# Ardy-Pro-Outlin-ev_3.net
KiCad netlist of a schematic drawn in EAGLE
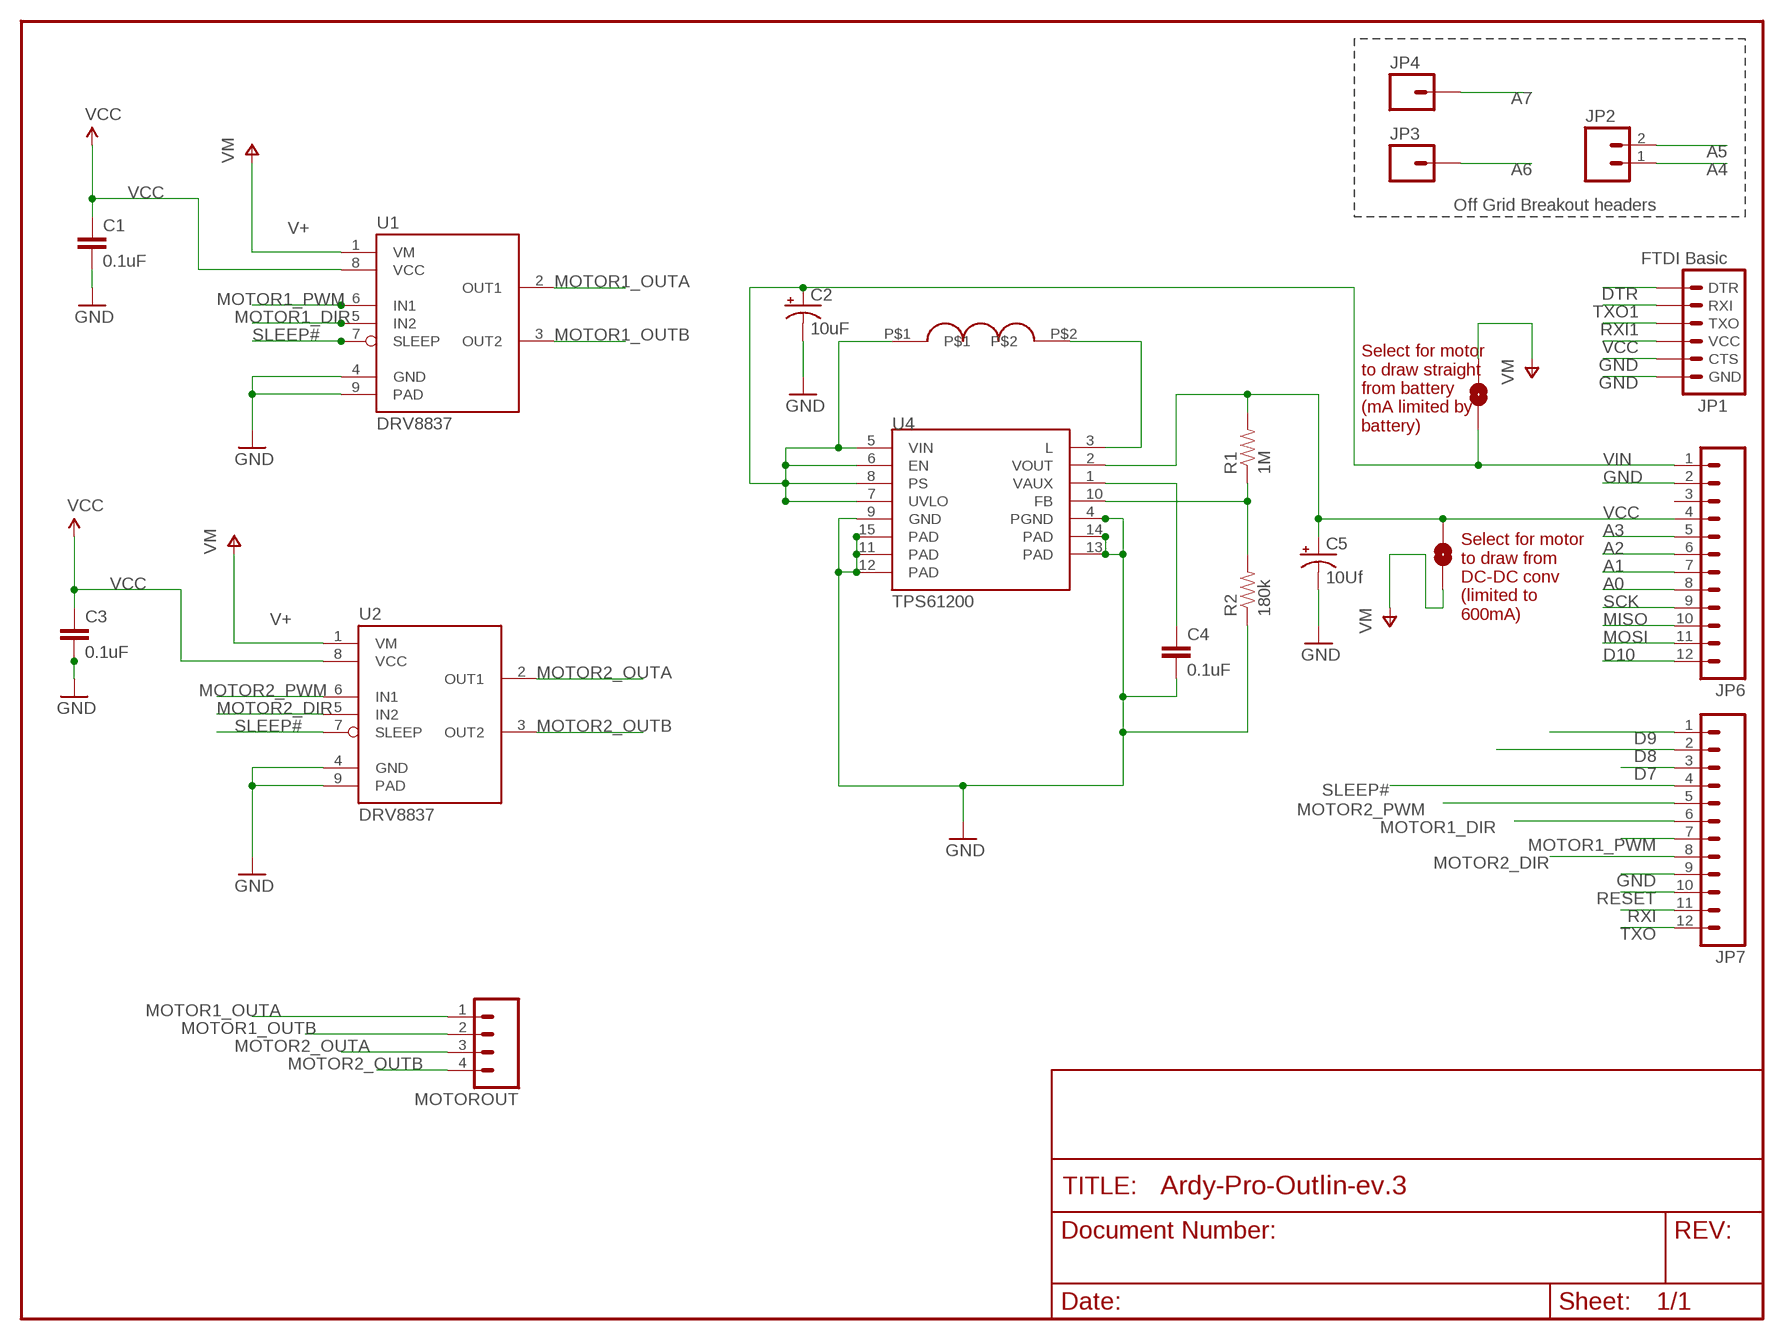
[diagram p0: schematic, sheet 1]

(export (version "E")
  (design (tool "Eeschema 10.0.6"))
  (components
    (comp (ref "2.2UH")
      (value "2.2uh")
      (footprint "eagle-import:PEBBLE_VLF4012A")
      (libsource (lib "eagle-import") (part "2.2UHSMD"))
    )
    (comp (ref "C1")
      (value "0.1uF")
      (footprint "eagle-import:0805")
      (libsource (lib "eagle-import") (part "CAP0805"))
    )
    (comp (ref "C2")
      (value "10uF")
      (footprint "eagle-import:EIA3216")
      (libsource (lib "eagle-import") (part "CAP_POL1206"))
    )
    (comp (ref "C3")
      (value "0.1uF")
      (footprint "eagle-import:0805")
      (libsource (lib "eagle-import") (part "CAP0805"))
    )
    (comp (ref "C4")
      (value "0.1uF")
      (footprint "eagle-import:0805")
      (libsource (lib "eagle-import") (part "CAP0805"))
    )
    (comp (ref "C5")
      (value "10Uf")
      (footprint "eagle-import:EIA3216")
      (libsource (lib "eagle-import") (part "CAP_POL1206"))
    )
    (comp (ref "JP1")
      (value "FTDI Basic")
      (footprint "eagle-import:1X06")
      (libsource (lib "eagle-import") (part "ARDUINO_SERIAL_PROGRAMPTH"))
    )
    (comp (ref "JP2")
      (value "M02PTH")
      (footprint "eagle-import:1X02")
      (libsource (lib "eagle-import") (part "M02PTH"))
    )
    (comp (ref "JP3")
      (value "M01PTH")
      (footprint "eagle-import:1X01")
      (libsource (lib "eagle-import") (part "M01PTH"))
    )
    (comp (ref "JP4")
      (value "M01PTH")
      (footprint "eagle-import:1X01")
      (libsource (lib "eagle-import") (part "M01PTH"))
    )
    (comp (ref "JP6")
      (value "M12PTH")
      (footprint "eagle-import:1X12")
      (libsource (lib "eagle-import") (part "M12PTH"))
    )
    (comp (ref "JP7")
      (value "M12PTH")
      (footprint "eagle-import:1X12")
      (libsource (lib "eagle-import") (part "M12PTH"))
    )
    (comp (ref "MOTOROUT")
      (value "M04PTH")
      (footprint "eagle-import:1X04")
      (libsource (lib "eagle-import") (part "M04PTH"))
    )
    (comp (ref "R1")
      (value "1M")
      (footprint "eagle-import:0805")
      (libsource (lib "eagle-import") (part "RESISTOR0805-RES"))
    )
    (comp (ref "R2")
      (value "180k")
      (footprint "eagle-import:0805")
      (libsource (lib "eagle-import") (part "RESISTOR0805-RES"))
    )
    (comp (ref "SJ1")
      (value "SOLDERJUMPERNO")
      (footprint "eagle-import:SJ_2S-NO")
      (libsource (lib "eagle-import") (part "SOLDERJUMPERNO"))
    )
    (comp (ref "SJ2")
      (value "SOLDERJUMPERNO")
      (footprint "eagle-import:SJ_2S-NO")
      (libsource (lib "eagle-import") (part "SOLDERJUMPERNO"))
    )
    (comp (ref "U1")
      (value "DRV8837")
      (footprint "eagle-import:WSON-8")
      (fields (field (name "PARTNO") "AS-ITM-00042"))
      (libsource (lib "eagle-import") (part "AS-ITM-00042"))
    )
    (comp (ref "U2")
      (value "DRV8837")
      (footprint "eagle-import:WSON-8")
      (fields (field (name "PARTNO") "AS-ITM-00042"))
      (libsource (lib "eagle-import") (part "AS-ITM-00042"))
    )
    (comp (ref "U4")
      (value "TPS61200")
      (footprint "eagle-import:QFN-10_PAD")
      (libsource (lib "eagle-import") (part "TPS61200"))
    )
  )
  (nets
    (net (code "1") (name "/A0") (class "Default")
      (node (ref "JP6") (pin "8") (pinfunction "8_8") (pintype "passive"))
    )
    (net (code "2") (name "/A1") (class "Default")
      (node (ref "JP6") (pin "7") (pinfunction "7_7") (pintype "passive"))
    )
    (net (code "3") (name "/A2") (class "Default")
      (node (ref "JP6") (pin "6") (pinfunction "6_6") (pintype "passive"))
    )
    (net (code "4") (name "/A3") (class "Default")
      (node (ref "JP6") (pin "5") (pinfunction "5_5") (pintype "passive"))
    )
    (net (code "5") (name "/A4") (class "Default")
      (node (ref "JP2") (pin "1") (pinfunction "1_1") (pintype "passive"))
    )
    (net (code "6") (name "/A5") (class "Default")
      (node (ref "JP2") (pin "2") (pinfunction "2_2") (pintype "passive"))
    )
    (net (code "7") (name "/A6") (class "Default")
      (node (ref "JP3") (pin "1") (pinfunction "1_1") (pintype "passive"))
    )
    (net (code "8") (name "/A7") (class "Default")
      (node (ref "JP4") (pin "1") (pinfunction "1_1") (pintype "passive"))
    )
    (net (code "9") (name "/D7") (class "Default")
      (node (ref "JP7") (pin "3") (pinfunction "3_3") (pintype "passive"))
    )
    (net (code "10") (name "/D8") (class "Default")
      (node (ref "JP7") (pin "2") (pinfunction "2_2") (pintype "passive"))
    )
    (net (code "11") (name "/D9") (class "Default")
      (node (ref "JP7") (pin "1") (pinfunction "1_1") (pintype "passive"))
    )
    (net (code "12") (name "/D10") (class "Default")
      (node (ref "JP6") (pin "12") (pinfunction "12_12") (pintype "passive"))
    )
    (net (code "13") (name "/DTR") (class "Default")
      (node (ref "JP1") (pin "1") (pinfunction "DTR_1") (pintype "passive"))
    )
    (net (code "14") (name "/MISO") (class "Default")
      (node (ref "JP6") (pin "10") (pinfunction "10_10") (pintype "passive"))
    )
    (net (code "15") (name "/MOSI") (class "Default")
      (node (ref "JP6") (pin "11") (pinfunction "11_11") (pintype "passive"))
    )
    (net (code "16") (name "/MOTOR1_DIR") (class "Default")
      (node (ref "JP7") (pin "6") (pinfunction "6_6") (pintype "passive"))
      (node (ref "U1") (pin "5") (pinfunction "IN2_5") (pintype "power_in"))
    )
    (net (code "17") (name "/MOTOR1_OUTA") (class "Default")
      (node (ref "MOTOROUT") (pin "1") (pinfunction "1_1") (pintype "passive"))
      (node (ref "U1") (pin "2") (pinfunction "OUT1_2") (pintype "bidirectional"))
    )
    (net (code "18") (name "/MOTOR1_OUTB") (class "Default")
      (node (ref "MOTOROUT") (pin "2") (pinfunction "2_2") (pintype "passive"))
      (node (ref "U1") (pin "3") (pinfunction "OUT2_3") (pintype "bidirectional"))
    )
    (net (code "19") (name "/MOTOR1_PWM") (class "Default")
      (node (ref "JP7") (pin "7") (pinfunction "7_7") (pintype "passive"))
      (node (ref "U1") (pin "6") (pinfunction "IN1_6") (pintype "power_in"))
    )
    (net (code "20") (name "/MOTOR2_DIR") (class "Default")
      (node (ref "JP7") (pin "8") (pinfunction "8_8") (pintype "passive"))
      (node (ref "U2") (pin "5") (pinfunction "IN2_5") (pintype "power_in"))
    )
    (net (code "21") (name "/MOTOR2_OUTA") (class "Default")
      (node (ref "MOTOROUT") (pin "3") (pinfunction "3_3") (pintype "passive"))
      (node (ref "U2") (pin "2") (pinfunction "OUT1_2") (pintype "bidirectional"))
    )
    (net (code "22") (name "/MOTOR2_OUTB") (class "Default")
      (node (ref "MOTOROUT") (pin "4") (pinfunction "4_4") (pintype "passive"))
      (node (ref "U2") (pin "3") (pinfunction "OUT2_3") (pintype "bidirectional"))
    )
    (net (code "23") (name "/MOTOR2_PWM") (class "Default")
      (node (ref "JP7") (pin "5") (pinfunction "5_5") (pintype "passive"))
      (node (ref "U2") (pin "6") (pinfunction "IN1_6") (pintype "power_in"))
    )
    (net (code "24") (name "/RESET") (class "Default")
      (node (ref "JP7") (pin "10") (pinfunction "10_10") (pintype "passive"))
    )
    (net (code "25") (name "/RXI") (class "Default")
      (node (ref "JP7") (pin "11") (pinfunction "11_11") (pintype "passive"))
    )
    (net (code "26") (name "/RXI1") (class "Default")
      (node (ref "JP1") (pin "3") (pinfunction "TXO_3") (pintype "passive"))
    )
    (net (code "27") (name "/SCK") (class "Default")
      (node (ref "JP6") (pin "9") (pinfunction "9_9") (pintype "passive"))
    )
    (net (code "28") (name "/SLEEP#") (class "Default")
      (node (ref "JP7") (pin "4") (pinfunction "4_4") (pintype "passive"))
      (node (ref "U1") (pin "7") (pinfunction "SLEEP_7") (pintype "bidirectional"))
      (node (ref "U2") (pin "7") (pinfunction "SLEEP_7") (pintype "bidirectional"))
    )
    (net (code "29") (name "/TXO") (class "Default")
      (node (ref "JP7") (pin "12") (pinfunction "12_12") (pintype "passive"))
    )
    (net (code "30") (name "/TXO1") (class "Default")
      (node (ref "JP1") (pin "2") (pinfunction "RXI_2") (pintype "passive"))
    )
    (net (code "31") (name "/VIN") (class "Default")
      (node (ref "2.2UH") (pin "P$1") (pinfunction "P$1_P$1") (pintype "bidirectional"))
      (node (ref "C2") (pin "A") (pinfunction "+_A") (pintype "passive"))
      (node (ref "JP6") (pin "1") (pinfunction "1_1") (pintype "passive"))
      (node (ref "SJ2") (pin "1") (pinfunction "1_1") (pintype "passive"))
      (node (ref "U4") (pin "5") (pinfunction "VIN_5") (pintype "power_in"))
      (node (ref "U4") (pin "6") (pinfunction "EN_6") (pintype "input"))
      (node (ref "U4") (pin "7") (pinfunction "UVLO_7") (pintype "passive"))
      (node (ref "U4") (pin "8") (pinfunction "PS_8") (pintype "input"))
    )
    (net (code "32") (name "GND") (class "Default")
      (node (ref "C1") (pin "2") (pinfunction "2_2") (pintype "passive"))
      (node (ref "C2") (pin "C") (pinfunction "-_C") (pintype "passive"))
      (node (ref "C3") (pin "2") (pinfunction "2_2") (pintype "passive"))
      (node (ref "C4") (pin "2") (pinfunction "2_2") (pintype "passive"))
      (node (ref "C5") (pin "C") (pinfunction "-_C") (pintype "passive"))
      (node (ref "JP1") (pin "5") (pinfunction "CTS_5") (pintype "passive"))
      (node (ref "JP1") (pin "6") (pinfunction "GND_6") (pintype "passive"))
      (node (ref "JP6") (pin "2") (pinfunction "2_2") (pintype "passive"))
      (node (ref "JP7") (pin "9") (pinfunction "9_9") (pintype "passive"))
      (node (ref "R2") (pin "1") (pinfunction "1_1") (pintype "passive"))
      (node (ref "U1") (pin "4") (pinfunction "GND_4") (pintype "power_in"))
      (node (ref "U1") (pin "9") (pinfunction "PAD_9") (pintype "power_in"))
      (node (ref "U2") (pin "4") (pinfunction "GND_4") (pintype "power_in"))
      (node (ref "U2") (pin "9") (pinfunction "PAD_9") (pintype "power_in"))
      (node (ref "U4") (pin "11") (pinfunction "PAD_11") (pintype "power_in"))
      (node (ref "U4") (pin "12") (pinfunction "PAD_12") (pintype "power_in"))
      (node (ref "U4") (pin "13") (pinfunction "PAD_13") (pintype "power_in"))
      (node (ref "U4") (pin "14") (pinfunction "PAD_14") (pintype "power_in"))
      (node (ref "U4") (pin "15") (pinfunction "PAD_15") (pintype "power_in"))
      (node (ref "U4") (pin "4") (pinfunction "PGND_4") (pintype "power_in"))
      (node (ref "U4") (pin "9") (pinfunction "GND_9") (pintype "power_in"))
    )
    (net (code "33") (name "Net-(U4-FB)") (class "Default")
      (node (ref "R1") (pin "1") (pinfunction "1_1") (pintype "passive"))
      (node (ref "R2") (pin "2") (pinfunction "2_2") (pintype "passive"))
      (node (ref "U4") (pin "10") (pinfunction "FB_10") (pintype "passive"))
    )
    (net (code "34") (name "Net-(U4-L)") (class "Default")
      (node (ref "2.2UH") (pin "P$2") (pinfunction "P$2_P$2") (pintype "bidirectional"))
      (node (ref "U4") (pin "3") (pinfunction "L_3") (pintype "passive"))
    )
    (net (code "35") (name "Net-(U4-VAUX)") (class "Default")
      (node (ref "C4") (pin "1") (pinfunction "1_1") (pintype "passive"))
      (node (ref "U4") (pin "1") (pinfunction "VAUX_1") (pintype "passive"))
    )
    (net (code "36") (name "VCC") (class "Default")
      (node (ref "C1") (pin "1") (pinfunction "1_1") (pintype "passive"))
      (node (ref "C3") (pin "1") (pinfunction "1_1") (pintype "passive"))
      (node (ref "C5") (pin "A") (pinfunction "+_A") (pintype "passive"))
      (node (ref "JP1") (pin "4") (pinfunction "VCC_4") (pintype "passive"))
      (node (ref "JP6") (pin "4") (pinfunction "4_4") (pintype "passive"))
      (node (ref "R1") (pin "2") (pinfunction "2_2") (pintype "passive"))
      (node (ref "SJ1") (pin "2") (pinfunction "2_2") (pintype "passive"))
      (node (ref "U1") (pin "8") (pinfunction "VCC_8") (pintype "bidirectional"))
      (node (ref "U2") (pin "8") (pinfunction "VCC_8") (pintype "bidirectional"))
      (node (ref "U4") (pin "2") (pinfunction "VOUT_2") (pintype "passive"))
    )
    (net (code "37") (name "VM") (class "Default")
      (node (ref "SJ1") (pin "1") (pinfunction "1_1") (pintype "passive"))
      (node (ref "SJ2") (pin "2") (pinfunction "2_2") (pintype "passive"))
      (node (ref "U1") (pin "1") (pinfunction "VM_1") (pintype "bidirectional"))
      (node (ref "U2") (pin "1") (pinfunction "VM_1") (pintype "bidirectional"))
    )
    (net (code "38") (name "unconnected-(JP6-Pad3)") (class "Default")
      (node (ref "JP6") (pin "3") (pinfunction "3_3") (pintype "passive"))
    )
  )
)
